# ioboard.net
KiCad netlist of a schematic drawn in EAGLE
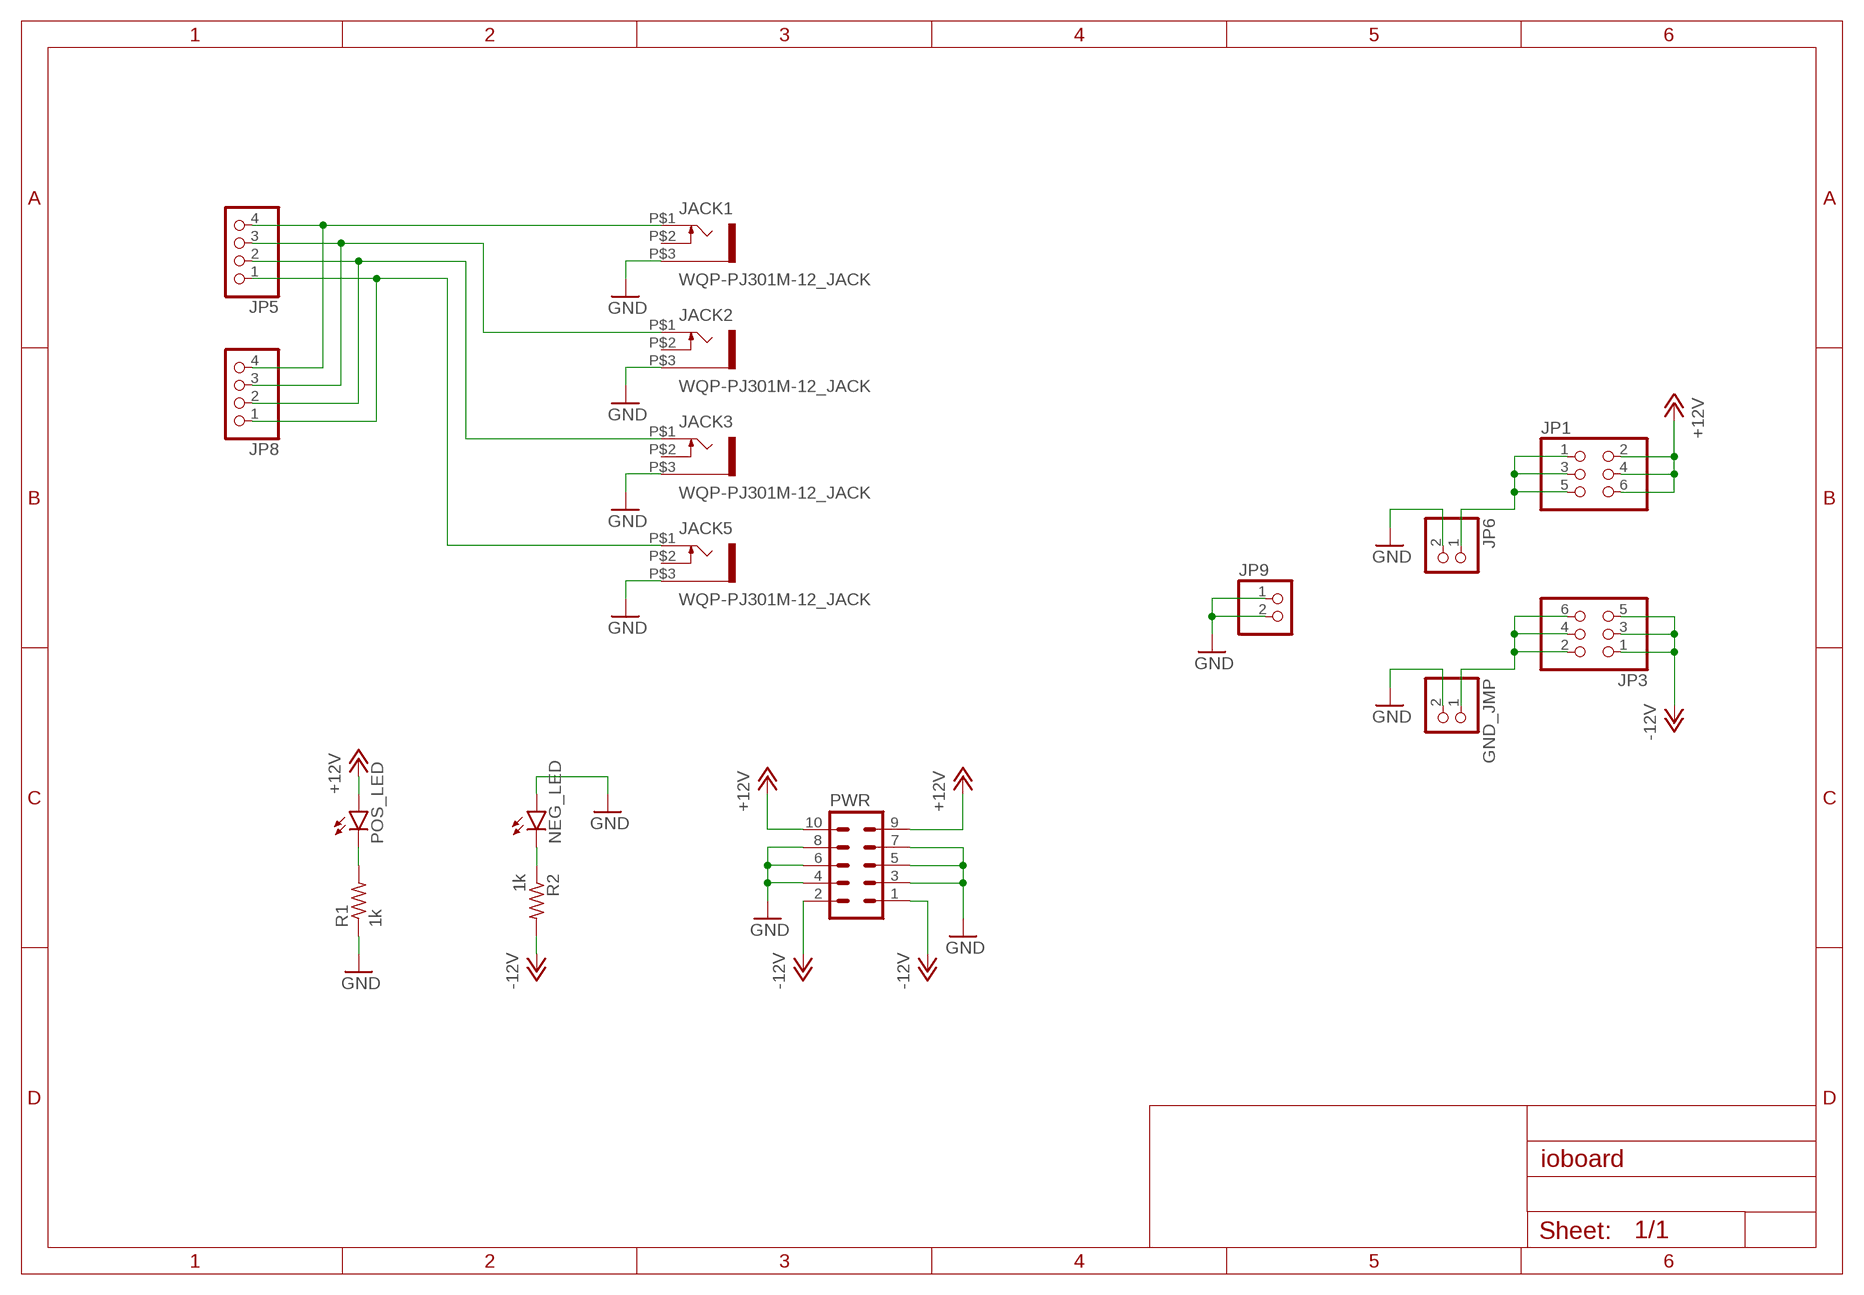
[diagram p0: schematic, sheet 1]

(export (version "E")
  (design (tool "Eeschema 10.0.6"))
  (components
    (comp (ref "GND_JMP")
      (value "PINHD-1X2")
      (footprint "eagle-import:1X02")
      (libsource (lib "eagle-import") (part "PINHD-1X2"))
    )
    (comp (ref "JACK1")
      (value "WQP-PJ301M-12_JACK")
      (footprint "eagle-import:WQP-PJ301M-12_JACK")
      (libsource (lib "eagle-import") (part "WQP-PJ301M-12_JACK"))
    )
    (comp (ref "JACK2")
      (value "WQP-PJ301M-12_JACK")
      (footprint "eagle-import:WQP-PJ301M-12_JACK")
      (libsource (lib "eagle-import") (part "WQP-PJ301M-12_JACK"))
    )
    (comp (ref "JACK3")
      (value "WQP-PJ301M-12_JACK")
      (footprint "eagle-import:WQP-PJ301M-12_JACK")
      (libsource (lib "eagle-import") (part "WQP-PJ301M-12_JACK"))
    )
    (comp (ref "JACK5")
      (value "WQP-PJ301M-12_JACK")
      (footprint "eagle-import:WQP-PJ301M-12_JACK")
      (libsource (lib "eagle-import") (part "WQP-PJ301M-12_JACK"))
    )
    (comp (ref "JP1")
      (value "PINHD-2X3")
      (footprint "eagle-import:2X03")
      (libsource (lib "eagle-import") (part "PINHD-2X3"))
    )
    (comp (ref "JP3")
      (value "PINHD-2X3")
      (footprint "eagle-import:2X03")
      (libsource (lib "eagle-import") (part "PINHD-2X3"))
    )
    (comp (ref "JP5")
      (value "PINHD-1X4")
      (footprint "eagle-import:1X04")
      (libsource (lib "eagle-import") (part "PINHD-1X4"))
    )
    (comp (ref "JP6")
      (value "PINHD-1X2")
      (footprint "eagle-import:1X02")
      (libsource (lib "eagle-import") (part "PINHD-1X2"))
    )
    (comp (ref "JP8")
      (value "PINHD-1X4")
      (footprint "eagle-import:1X04")
      (libsource (lib "eagle-import") (part "PINHD-1X4"))
    )
    (comp (ref "JP9")
      (value "PINHD-1X2")
      (footprint "eagle-import:1X02")
      (libsource (lib "eagle-import") (part "PINHD-1X2"))
    )
    (comp (ref "NEG_LED")
      (value "LED3MM")
      (footprint "eagle-import:LED3MM")
      (libsource (lib "eagle-import") (part "LED3MM"))
    )
    (comp (ref "POS_LED")
      (value "LED3MM")
      (footprint "eagle-import:LED3MM")
      (libsource (lib "eagle-import") (part "LED3MM"))
    )
    (comp (ref "PWR")
      (value "ML10")
      (footprint "eagle-import:ML10")
      (libsource (lib "eagle-import") (part "ML10"))
    )
    (comp (ref "R1")
      (value "1k")
      (footprint "eagle-import:0207_7")
      (libsource (lib "eagle-import") (part "R-US_0207/7"))
    )
    (comp (ref "R2")
      (value "1k")
      (footprint "eagle-import:0207_7")
      (libsource (lib "eagle-import") (part "R-US_0207/7"))
    )
  )
  (nets
    (net (code "1") (name "+12V") (class "Default")
      (node (ref "JP1") (pin "2") (pinfunction "2_2") (pintype "passive"))
      (node (ref "JP1") (pin "4") (pinfunction "4_4") (pintype "passive"))
      (node (ref "JP1") (pin "6") (pinfunction "6_6") (pintype "passive"))
      (node (ref "POS_LED") (pin "A") (pinfunction "A_A") (pintype "passive"))
      (node (ref "PWR") (pin "10") (pinfunction "10_10") (pintype "passive"))
      (node (ref "PWR") (pin "9") (pinfunction "9_9") (pintype "passive"))
    )
    (net (code "2") (name "-12V") (class "Default")
      (node (ref "JP3") (pin "1") (pinfunction "1_1") (pintype "passive"))
      (node (ref "JP3") (pin "3") (pinfunction "3_3") (pintype "passive"))
      (node (ref "JP3") (pin "5") (pinfunction "5_5") (pintype "passive"))
      (node (ref "PWR") (pin "1") (pinfunction "1_1") (pintype "passive"))
      (node (ref "PWR") (pin "2") (pinfunction "2_2") (pintype "passive"))
      (node (ref "R2") (pin "2") (pinfunction "2_2") (pintype "passive"))
    )
    (net (code "3") (name "GND") (class "Default")
      (node (ref "GND_JMP") (pin "2") (pinfunction "2_2") (pintype "passive"))
      (node (ref "JACK1") (pin "P$3") (pinfunction "1_P$3") (pintype "passive"))
      (node (ref "JACK2") (pin "P$3") (pinfunction "1_P$3") (pintype "passive"))
      (node (ref "JACK3") (pin "P$3") (pinfunction "1_P$3") (pintype "passive"))
      (node (ref "JACK5") (pin "P$3") (pinfunction "1_P$3") (pintype "passive"))
      (node (ref "JP6") (pin "2") (pinfunction "2_2") (pintype "passive"))
      (node (ref "JP9") (pin "1") (pinfunction "1_1") (pintype "passive"))
      (node (ref "JP9") (pin "2") (pinfunction "2_2") (pintype "passive"))
      (node (ref "NEG_LED") (pin "A") (pinfunction "A_A") (pintype "passive"))
      (node (ref "PWR") (pin "3") (pinfunction "3_3") (pintype "passive"))
      (node (ref "PWR") (pin "4") (pinfunction "4_4") (pintype "passive"))
      (node (ref "PWR") (pin "5") (pinfunction "5_5") (pintype "passive"))
      (node (ref "PWR") (pin "6") (pinfunction "6_6") (pintype "passive"))
      (node (ref "PWR") (pin "7") (pinfunction "7_7") (pintype "passive"))
      (node (ref "PWR") (pin "8") (pinfunction "8_8") (pintype "passive"))
      (node (ref "R1") (pin "1") (pinfunction "1_1") (pintype "passive"))
    )
    (net (code "4") (name "Net-(GND_JMP-Pad1)") (class "Default")
      (node (ref "GND_JMP") (pin "1") (pinfunction "1_1") (pintype "passive"))
      (node (ref "JP3") (pin "2") (pinfunction "2_2") (pintype "passive"))
      (node (ref "JP3") (pin "4") (pinfunction "4_4") (pintype "passive"))
      (node (ref "JP3") (pin "6") (pinfunction "6_6") (pintype "passive"))
    )
    (net (code "5") (name "Net-(JACK1-2)") (class "Default")
      (node (ref "JACK1") (pin "P$1") (pinfunction "2_P$1") (pintype "passive"))
      (node (ref "JP5") (pin "4") (pinfunction "4_4") (pintype "passive"))
      (node (ref "JP8") (pin "4") (pinfunction "4_4") (pintype "passive"))
    )
    (net (code "6") (name "Net-(JACK2-2)") (class "Default")
      (node (ref "JACK2") (pin "P$1") (pinfunction "2_P$1") (pintype "passive"))
      (node (ref "JP5") (pin "3") (pinfunction "3_3") (pintype "passive"))
      (node (ref "JP8") (pin "3") (pinfunction "3_3") (pintype "passive"))
    )
    (net (code "7") (name "Net-(JACK3-2)") (class "Default")
      (node (ref "JACK3") (pin "P$1") (pinfunction "2_P$1") (pintype "passive"))
      (node (ref "JP5") (pin "2") (pinfunction "2_2") (pintype "passive"))
      (node (ref "JP8") (pin "2") (pinfunction "2_2") (pintype "passive"))
    )
    (net (code "8") (name "Net-(JACK5-2)") (class "Default")
      (node (ref "JACK5") (pin "P$1") (pinfunction "2_P$1") (pintype "passive"))
      (node (ref "JP5") (pin "1") (pinfunction "1_1") (pintype "passive"))
      (node (ref "JP8") (pin "1") (pinfunction "1_1") (pintype "passive"))
    )
    (net (code "9") (name "Net-(JP1-Pad1)") (class "Default")
      (node (ref "JP1") (pin "1") (pinfunction "1_1") (pintype "passive"))
      (node (ref "JP1") (pin "3") (pinfunction "3_3") (pintype "passive"))
      (node (ref "JP1") (pin "5") (pinfunction "5_5") (pintype "passive"))
      (node (ref "JP6") (pin "1") (pinfunction "1_1") (pintype "passive"))
    )
    (net (code "10") (name "Net-(NEG_LED-C)") (class "Default")
      (node (ref "NEG_LED") (pin "K") (pinfunction "C_K") (pintype "passive"))
      (node (ref "R2") (pin "1") (pinfunction "1_1") (pintype "passive"))
    )
    (net (code "11") (name "Net-(POS_LED-C)") (class "Default")
      (node (ref "POS_LED") (pin "K") (pinfunction "C_K") (pintype "passive"))
      (node (ref "R1") (pin "2") (pinfunction "2_2") (pintype "passive"))
    )
    (net (code "12") (name "unconnected-(JACK1-3-PadP$2)") (class "Default")
      (node (ref "JACK1") (pin "P$2") (pinfunction "3_P$2") (pintype "passive"))
    )
    (net (code "13") (name "unconnected-(JACK2-3-PadP$2)") (class "Default")
      (node (ref "JACK2") (pin "P$2") (pinfunction "3_P$2") (pintype "passive"))
    )
    (net (code "14") (name "unconnected-(JACK3-3-PadP$2)") (class "Default")
      (node (ref "JACK3") (pin "P$2") (pinfunction "3_P$2") (pintype "passive"))
    )
    (net (code "15") (name "unconnected-(JACK5-3-PadP$2)") (class "Default")
      (node (ref "JACK5") (pin "P$2") (pinfunction "3_P$2") (pintype "passive"))
    )
  )
)
